# TubeScreamer.net
KiCad netlist of a schematic drawn in EAGLE
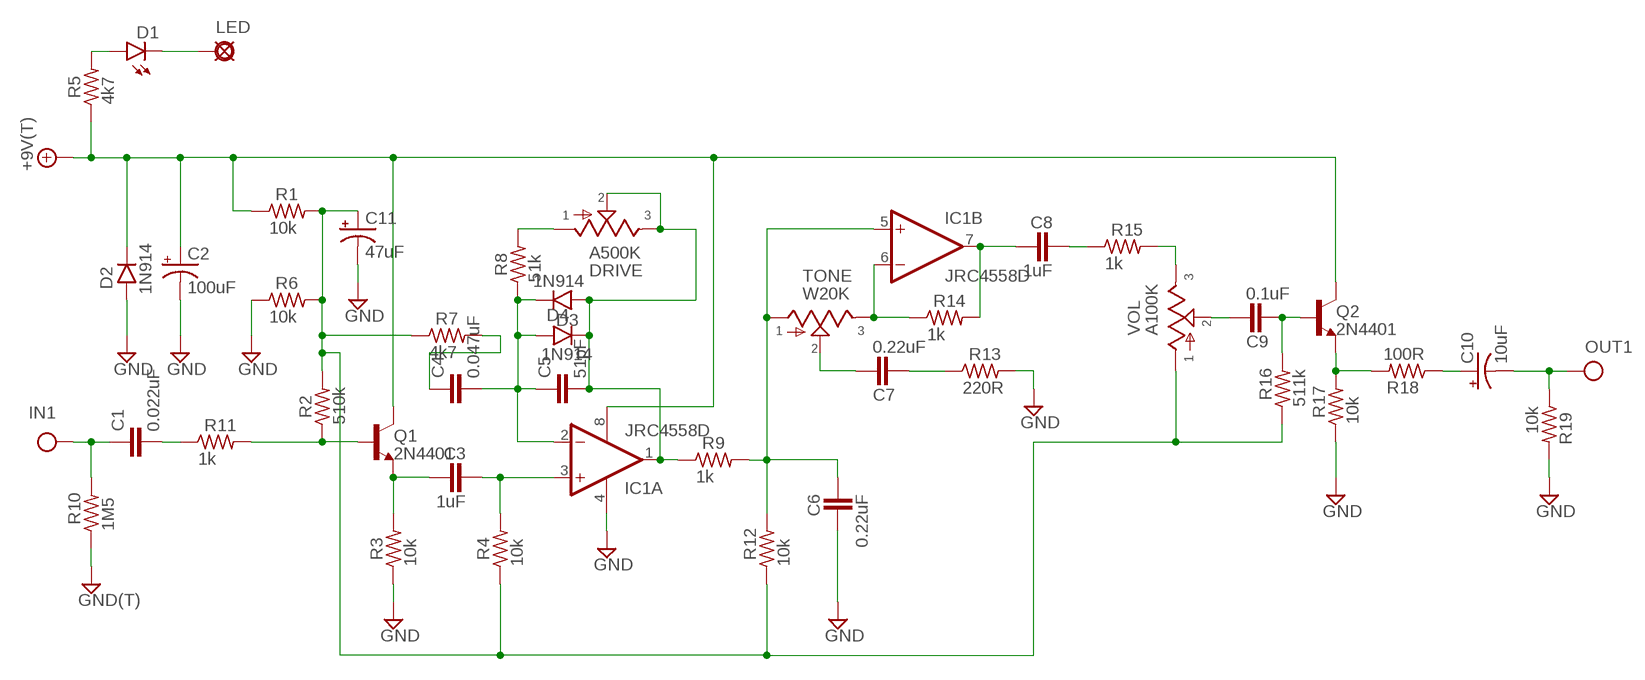
[diagram p0: schematic, sheet 1]

(export (version "E")
  (design (tool "Eeschema 10.0.6"))
  (components
    (comp (ref "+9V1")
      (value "+9V(T)")
      (footprint "eagle-import:SQUARE")
      (libsource (lib "eagle-import") (part "+9V(T)"))
    )
    (comp (ref "C1")
      (value "0.022uF")
      (footprint "eagle-import:070X030")
      (libsource (lib "eagle-import") (part "070X0302"))
    )
    (comp (ref "C2")
      (value "100uF")
      (footprint "eagle-import:080_035")
      (libsource (lib "eagle-import") (part "080"))
    )
    (comp (ref "C3")
      (value "1uF")
      (footprint "eagle-import:072X035")
      (libsource (lib "eagle-import") (part "072X0352"))
    )
    (comp (ref "C4")
      (value "0.047uF")
      (footprint "eagle-import:070X030")
      (libsource (lib "eagle-import") (part "070X0302"))
    )
    (comp (ref "C5")
      (value "51pF")
      (footprint "eagle-import:050X030_025")
      (libsource (lib "eagle-import") (part "050X030_0251"))
    )
    (comp (ref "C6")
      (value "0.22uF")
      (footprint "eagle-import:072X035")
      (libsource (lib "eagle-import") (part "072X0352"))
    )
    (comp (ref "C7")
      (value "0.22uF")
      (footprint "eagle-import:072X035")
      (libsource (lib "eagle-import") (part "072X0352"))
    )
    (comp (ref "C8")
      (value "1uF")
      (footprint "eagle-import:072X035")
      (libsource (lib "eagle-import") (part "072X0352"))
    )
    (comp (ref "C9")
      (value "0.1uF")
      (footprint "eagle-import:072X035")
      (libsource (lib "eagle-import") (part "072X0352"))
    )
    (comp (ref "C10")
      (value "10uF")
      (footprint "eagle-import:063_025")
      (libsource (lib "eagle-import") (part "0631"))
    )
    (comp (ref "C11")
      (value "47uF")
      (footprint "eagle-import:063_025")
      (libsource (lib "eagle-import") (part "0631"))
    )
    (comp (ref "D1")
      (value "LED3MM")
      (footprint "eagle-import:LED3MM")
      (libsource (lib "eagle-import") (part "LED3MM"))
    )
    (comp (ref "D2")
      (value "1N914")
      (footprint "eagle-import:DO35-3")
      (libsource (lib "eagle-import") (part "1N914.3"))
    )
    (comp (ref "D3")
      (value "1N914")
      (footprint "eagle-import:DO35-3")
      (libsource (lib "eagle-import") (part "1N914.3"))
    )
    (comp (ref "D4")
      (value "1N914")
      (footprint "eagle-import:DO35-3")
      (libsource (lib "eagle-import") (part "1N914.3"))
    )
    (comp (ref "DRIVE")
      (value "A500K")
      (footprint "eagle-import:16MM")
      (libsource (lib "eagle-import") (part "POT16MM"))
    )
    (comp (ref "GND1")
      (value "GND(T)")
      (footprint "eagle-import:SQUARE")
      (libsource (lib "eagle-import") (part "GND(T)"))
    )
    (comp (ref "IC1")
      (value "JRC4558D")
      (footprint "eagle-import:DIL08")
      (libsource (lib "eagle-import") (part "4558NLM"))
    )
    (comp (ref "IN1")
      (value "IN(T)")
      (footprint "eagle-import:SQUARE")
      (libsource (lib "eagle-import") (part "IN(T)"))
    )
    (comp (ref "LED")
      (value "3mm")
      (footprint "eagle-import:SQUARE")
      (libsource (lib "eagle-import") (part "PAD"))
    )
    (comp (ref "OUT1")
      (value "OUT(T)")
      (footprint "eagle-import:SQUARE")
      (libsource (lib "eagle-import") (part "OUT(T)"))
    )
    (comp (ref "Q1")
      (value "2N4401")
      (footprint "eagle-import:TO92-")
      (libsource (lib "eagle-import") (part "2N3904"))
    )
    (comp (ref "Q2")
      (value "2N4401")
      (footprint "eagle-import:TO92-")
      (libsource (lib "eagle-import") (part "2N3904"))
    )
    (comp (ref "R1")
      (value "10k")
      (footprint "eagle-import:R0207_3")
      (libsource (lib "eagle-import") (part "6MM.3"))
    )
    (comp (ref "R2")
      (value "510k")
      (footprint "eagle-import:R0207_3")
      (libsource (lib "eagle-import") (part "6MM.3"))
    )
    (comp (ref "R3")
      (value "10k")
      (footprint "eagle-import:R0207_3")
      (libsource (lib "eagle-import") (part "6MM.3"))
    )
    (comp (ref "R4")
      (value "10k")
      (footprint "eagle-import:R0207_3")
      (libsource (lib "eagle-import") (part "6MM.3"))
    )
    (comp (ref "R5")
      (value "4k7")
      (footprint "eagle-import:R0207_3")
      (libsource (lib "eagle-import") (part "6MM.3"))
    )
    (comp (ref "R6")
      (value "10k")
      (footprint "eagle-import:R0207_3")
      (libsource (lib "eagle-import") (part "6MM.3"))
    )
    (comp (ref "R7")
      (value "4k7")
      (footprint "eagle-import:R0207_3")
      (libsource (lib "eagle-import") (part "6MM.3"))
    )
    (comp (ref "R8")
      (value "51k")
      (footprint "eagle-import:R0207_3")
      (libsource (lib "eagle-import") (part "6MM.3"))
    )
    (comp (ref "R9")
      (value "1k")
      (footprint "eagle-import:R0207_3")
      (libsource (lib "eagle-import") (part "6MM.3"))
    )
    (comp (ref "R10")
      (value "1M5")
      (footprint "eagle-import:R0207_3")
      (libsource (lib "eagle-import") (part "6MM.3"))
    )
    (comp (ref "R11")
      (value "1k")
      (footprint "eagle-import:R0207_3")
      (libsource (lib "eagle-import") (part "6MM.3"))
    )
    (comp (ref "R12")
      (value "10k")
      (footprint "eagle-import:R0207_3")
      (libsource (lib "eagle-import") (part "6MM.3"))
    )
    (comp (ref "R13")
      (value "220R")
      (footprint "eagle-import:R0207_3")
      (libsource (lib "eagle-import") (part "6MM.3"))
    )
    (comp (ref "R14")
      (value "1k")
      (footprint "eagle-import:R0207_3")
      (libsource (lib "eagle-import") (part "6MM.3"))
    )
    (comp (ref "R15")
      (value "1k")
      (footprint "eagle-import:R0207_3")
      (libsource (lib "eagle-import") (part "6MM.3"))
    )
    (comp (ref "R16")
      (value "511k")
      (footprint "eagle-import:R0207_3")
      (libsource (lib "eagle-import") (part "6MM.3"))
    )
    (comp (ref "R17")
      (value "10k")
      (footprint "eagle-import:R0207_3")
      (libsource (lib "eagle-import") (part "6MM.3"))
    )
    (comp (ref "R18")
      (value "100R")
      (footprint "eagle-import:R0207_3")
      (libsource (lib "eagle-import") (part "6MM.3"))
    )
    (comp (ref "R19")
      (value "10k")
      (footprint "eagle-import:R0207_3")
      (libsource (lib "eagle-import") (part "6MM.3"))
    )
    (comp (ref "TONE")
      (value "W20K")
      (footprint "eagle-import:16MM")
      (libsource (lib "eagle-import") (part "POT16MM"))
    )
    (comp (ref "VOL")
      (value "A100K")
      (footprint "eagle-import:16MM")
      (libsource (lib "eagle-import") (part "POT16MM"))
    )
  )
  (nets
    (net (code "1") (name "+9V(T)") (class "Default")
      (node (ref "+9V1") (pin "1") (pinfunction "+9V_1") (pintype "power_in"))
      (node (ref "C2") (pin "+") (pinfunction "+_+") (pintype "passive"))
      (node (ref "D2") (pin "C") (pinfunction "C_C") (pintype "passive"))
      (node (ref "IC1") (pin "8") (pinfunction "V+_8") (pintype "power_in"))
      (node (ref "Q1") (pin "1") (pinfunction "C_1") (pintype "passive"))
      (node (ref "Q2") (pin "1") (pinfunction "C_1") (pintype "passive"))
      (node (ref "R1") (pin "1") (pinfunction "1_1") (pintype "passive"))
      (node (ref "R5") (pin "1") (pinfunction "1_1") (pintype "passive"))
    )
    (net (code "2") (name "GND") (class "Default")
      (node (ref "C11") (pin "-") (pinfunction "-_-") (pintype "passive"))
      (node (ref "C2") (pin "-") (pinfunction "-_-") (pintype "passive"))
      (node (ref "C6") (pin "1") (pinfunction "1_1") (pintype "passive"))
      (node (ref "D2") (pin "A") (pinfunction "A_A") (pintype "passive"))
      (node (ref "GND1") (pin "1") (pinfunction "GND_1") (pintype "power_in"))
      (node (ref "IC1") (pin "4") (pinfunction "V-_4") (pintype "power_in"))
      (node (ref "R10") (pin "1") (pinfunction "1_1") (pintype "passive"))
      (node (ref "R13") (pin "2") (pinfunction "2_2") (pintype "passive"))
      (node (ref "R17") (pin "1") (pinfunction "1_1") (pintype "passive"))
      (node (ref "R19") (pin "2") (pinfunction "2_2") (pintype "passive"))
      (node (ref "R3") (pin "1") (pinfunction "1_1") (pintype "passive"))
      (node (ref "R6") (pin "1") (pinfunction "1_1") (pintype "passive"))
    )
    (net (code "3") (name "IN(T)") (class "Default")
      (node (ref "C1") (pin "1") (pinfunction "1_1") (pintype "passive"))
      (node (ref "IN1") (pin "1") (pinfunction "IN_1") (pintype "power_in"))
      (node (ref "R10") (pin "2") (pinfunction "2_2") (pintype "passive"))
    )
    (net (code "4") (name "Net-(C1-Pad2)") (class "Default")
      (node (ref "C1") (pin "2") (pinfunction "2_2") (pintype "passive"))
      (node (ref "R11") (pin "1") (pinfunction "1_1") (pintype "passive"))
    )
    (net (code "5") (name "Net-(C4-Pad1)") (class "Default")
      (node (ref "C4") (pin "1") (pinfunction "1_1") (pintype "passive"))
      (node (ref "R7") (pin "2") (pinfunction "2_2") (pintype "passive"))
    )
    (net (code "6") (name "Net-(C7-Pad1)") (class "Default")
      (node (ref "C7") (pin "1") (pinfunction "1_1") (pintype "passive"))
      (node (ref "R13") (pin "1") (pinfunction "1_1") (pintype "passive"))
    )
    (net (code "7") (name "Net-(C7-Pad2)") (class "Default")
      (node (ref "C7") (pin "2") (pinfunction "2_2") (pintype "passive"))
      (node (ref "TONE") (pin "2") (pinfunction "2_2") (pintype "passive"))
    )
    (net (code "8") (name "Net-(C8-Pad2)") (class "Default")
      (node (ref "C8") (pin "2") (pinfunction "2_2") (pintype "passive"))
      (node (ref "R15") (pin "1") (pinfunction "1_1") (pintype "passive"))
    )
    (net (code "9") (name "Net-(C9-Pad2)") (class "Default")
      (node (ref "C9") (pin "2") (pinfunction "2_2") (pintype "passive"))
      (node (ref "VOL") (pin "2") (pinfunction "2_2") (pintype "passive"))
    )
    (net (code "10") (name "Net-(C10-Pad+)") (class "Default")
      (node (ref "C10") (pin "+") (pinfunction "+_+") (pintype "passive"))
      (node (ref "R18") (pin "1") (pinfunction "1_1") (pintype "passive"))
    )
    (net (code "11") (name "Net-(C11-Pad+)") (class "Default")
      (node (ref "C11") (pin "+") (pinfunction "+_+") (pintype "passive"))
      (node (ref "R1") (pin "2") (pinfunction "2_2") (pintype "passive"))
      (node (ref "R12") (pin "1") (pinfunction "1_1") (pintype "passive"))
      (node (ref "R16") (pin "1") (pinfunction "1_1") (pintype "passive"))
      (node (ref "R2") (pin "2") (pinfunction "2_2") (pintype "passive"))
      (node (ref "R4") (pin "1") (pinfunction "1_1") (pintype "passive"))
      (node (ref "R6") (pin "2") (pinfunction "2_2") (pintype "passive"))
      (node (ref "R7") (pin "1") (pinfunction "1_1") (pintype "passive"))
      (node (ref "VOL") (pin "1") (pinfunction "1_1") (pintype "passive"))
    )
    (net (code "12") (name "Net-(D1-C)") (class "Default")
      (node (ref "D1") (pin "K") (pinfunction "C_K") (pintype "passive"))
      (node (ref "LED") (pin "1") (pinfunction "PAD_1") (pintype "passive"))
    )
    (net (code "13") (name "Net-(D1-PadA)") (class "Default")
      (node (ref "D1") (pin "A") (pinfunction "A_A") (pintype "passive"))
      (node (ref "R5") (pin "2") (pinfunction "2_2") (pintype "passive"))
    )
    (net (code "14") (name "Net-(DRIVE-Pad1)") (class "Default")
      (node (ref "DRIVE") (pin "1") (pinfunction "1_1") (pintype "passive"))
      (node (ref "R8") (pin "2") (pinfunction "2_2") (pintype "passive"))
    )
    (net (code "15") (name "Net-(IC1A-+IN)") (class "Default")
      (node (ref "C3") (pin "2") (pinfunction "2_2") (pintype "passive"))
      (node (ref "IC1") (pin "3") (pinfunction "+IN_3") (pintype "input"))
      (node (ref "R4") (pin "2") (pinfunction "2_2") (pintype "passive"))
    )
    (net (code "16") (name "Net-(IC1A--IN)") (class "Default")
      (node (ref "C4") (pin "2") (pinfunction "2_2") (pintype "passive"))
      (node (ref "C5") (pin "1") (pinfunction "1_1") (pintype "passive"))
      (node (ref "D3") (pin "C") (pinfunction "C_C") (pintype "passive"))
      (node (ref "D4") (pin "A") (pinfunction "A_A") (pintype "passive"))
      (node (ref "IC1") (pin "2") (pinfunction "-IN_2") (pintype "input"))
      (node (ref "R8") (pin "1") (pinfunction "1_1") (pintype "passive"))
    )
    (net (code "17") (name "Net-(IC1A-OUT)") (class "Default")
      (node (ref "C5") (pin "2") (pinfunction "2_2") (pintype "passive"))
      (node (ref "D3") (pin "A") (pinfunction "A_A") (pintype "passive"))
      (node (ref "D4") (pin "C") (pinfunction "C_C") (pintype "passive"))
      (node (ref "DRIVE") (pin "2") (pinfunction "2_2") (pintype "passive"))
      (node (ref "DRIVE") (pin "3") (pinfunction "3_3") (pintype "passive"))
      (node (ref "IC1") (pin "1") (pinfunction "OUT_1") (pintype "output"))
      (node (ref "R9") (pin "1") (pinfunction "1_1") (pintype "passive"))
    )
    (net (code "18") (name "Net-(IC1B-+IN)") (class "Default")
      (node (ref "C6") (pin "2") (pinfunction "2_2") (pintype "passive"))
      (node (ref "IC1") (pin "5") (pinfunction "+IN_5") (pintype "input"))
      (node (ref "R12") (pin "2") (pinfunction "2_2") (pintype "passive"))
      (node (ref "R9") (pin "2") (pinfunction "2_2") (pintype "passive"))
      (node (ref "TONE") (pin "1") (pinfunction "1_1") (pintype "passive"))
    )
    (net (code "19") (name "Net-(IC1B--IN)") (class "Default")
      (node (ref "IC1") (pin "6") (pinfunction "-IN_6") (pintype "input"))
      (node (ref "R14") (pin "1") (pinfunction "1_1") (pintype "passive"))
      (node (ref "TONE") (pin "3") (pinfunction "3_3") (pintype "passive"))
    )
    (net (code "20") (name "Net-(IC1B-OUT)") (class "Default")
      (node (ref "C8") (pin "1") (pinfunction "1_1") (pintype "passive"))
      (node (ref "IC1") (pin "7") (pinfunction "OUT_7") (pintype "output"))
      (node (ref "R14") (pin "2") (pinfunction "2_2") (pintype "passive"))
    )
    (net (code "21") (name "Net-(Q1-B)") (class "Default")
      (node (ref "Q1") (pin "2") (pinfunction "B_2") (pintype "passive"))
      (node (ref "R11") (pin "2") (pinfunction "2_2") (pintype "passive"))
      (node (ref "R2") (pin "1") (pinfunction "1_1") (pintype "passive"))
    )
    (net (code "22") (name "Net-(Q1-E)") (class "Default")
      (node (ref "C3") (pin "1") (pinfunction "1_1") (pintype "passive"))
      (node (ref "Q1") (pin "3") (pinfunction "E_3") (pintype "passive"))
      (node (ref "R3") (pin "2") (pinfunction "2_2") (pintype "passive"))
    )
    (net (code "23") (name "Net-(Q2-B)") (class "Default")
      (node (ref "C9") (pin "1") (pinfunction "1_1") (pintype "passive"))
      (node (ref "Q2") (pin "2") (pinfunction "B_2") (pintype "passive"))
      (node (ref "R16") (pin "2") (pinfunction "2_2") (pintype "passive"))
    )
    (net (code "24") (name "Net-(Q2-E)") (class "Default")
      (node (ref "Q2") (pin "3") (pinfunction "E_3") (pintype "passive"))
      (node (ref "R17") (pin "2") (pinfunction "2_2") (pintype "passive"))
      (node (ref "R18") (pin "2") (pinfunction "2_2") (pintype "passive"))
    )
    (net (code "25") (name "Net-(R15-Pad2)") (class "Default")
      (node (ref "R15") (pin "2") (pinfunction "2_2") (pintype "passive"))
      (node (ref "VOL") (pin "3") (pinfunction "3_3") (pintype "passive"))
    )
    (net (code "26") (name "OUT(T)") (class "Default")
      (node (ref "C10") (pin "-") (pinfunction "-_-") (pintype "passive"))
      (node (ref "OUT1") (pin "1") (pinfunction "OUT_1") (pintype "power_in"))
      (node (ref "R19") (pin "1") (pinfunction "1_1") (pintype "passive"))
    )
  )
)
